# schematic.net
KiCad netlist of a schematic drawn in Altium Designer
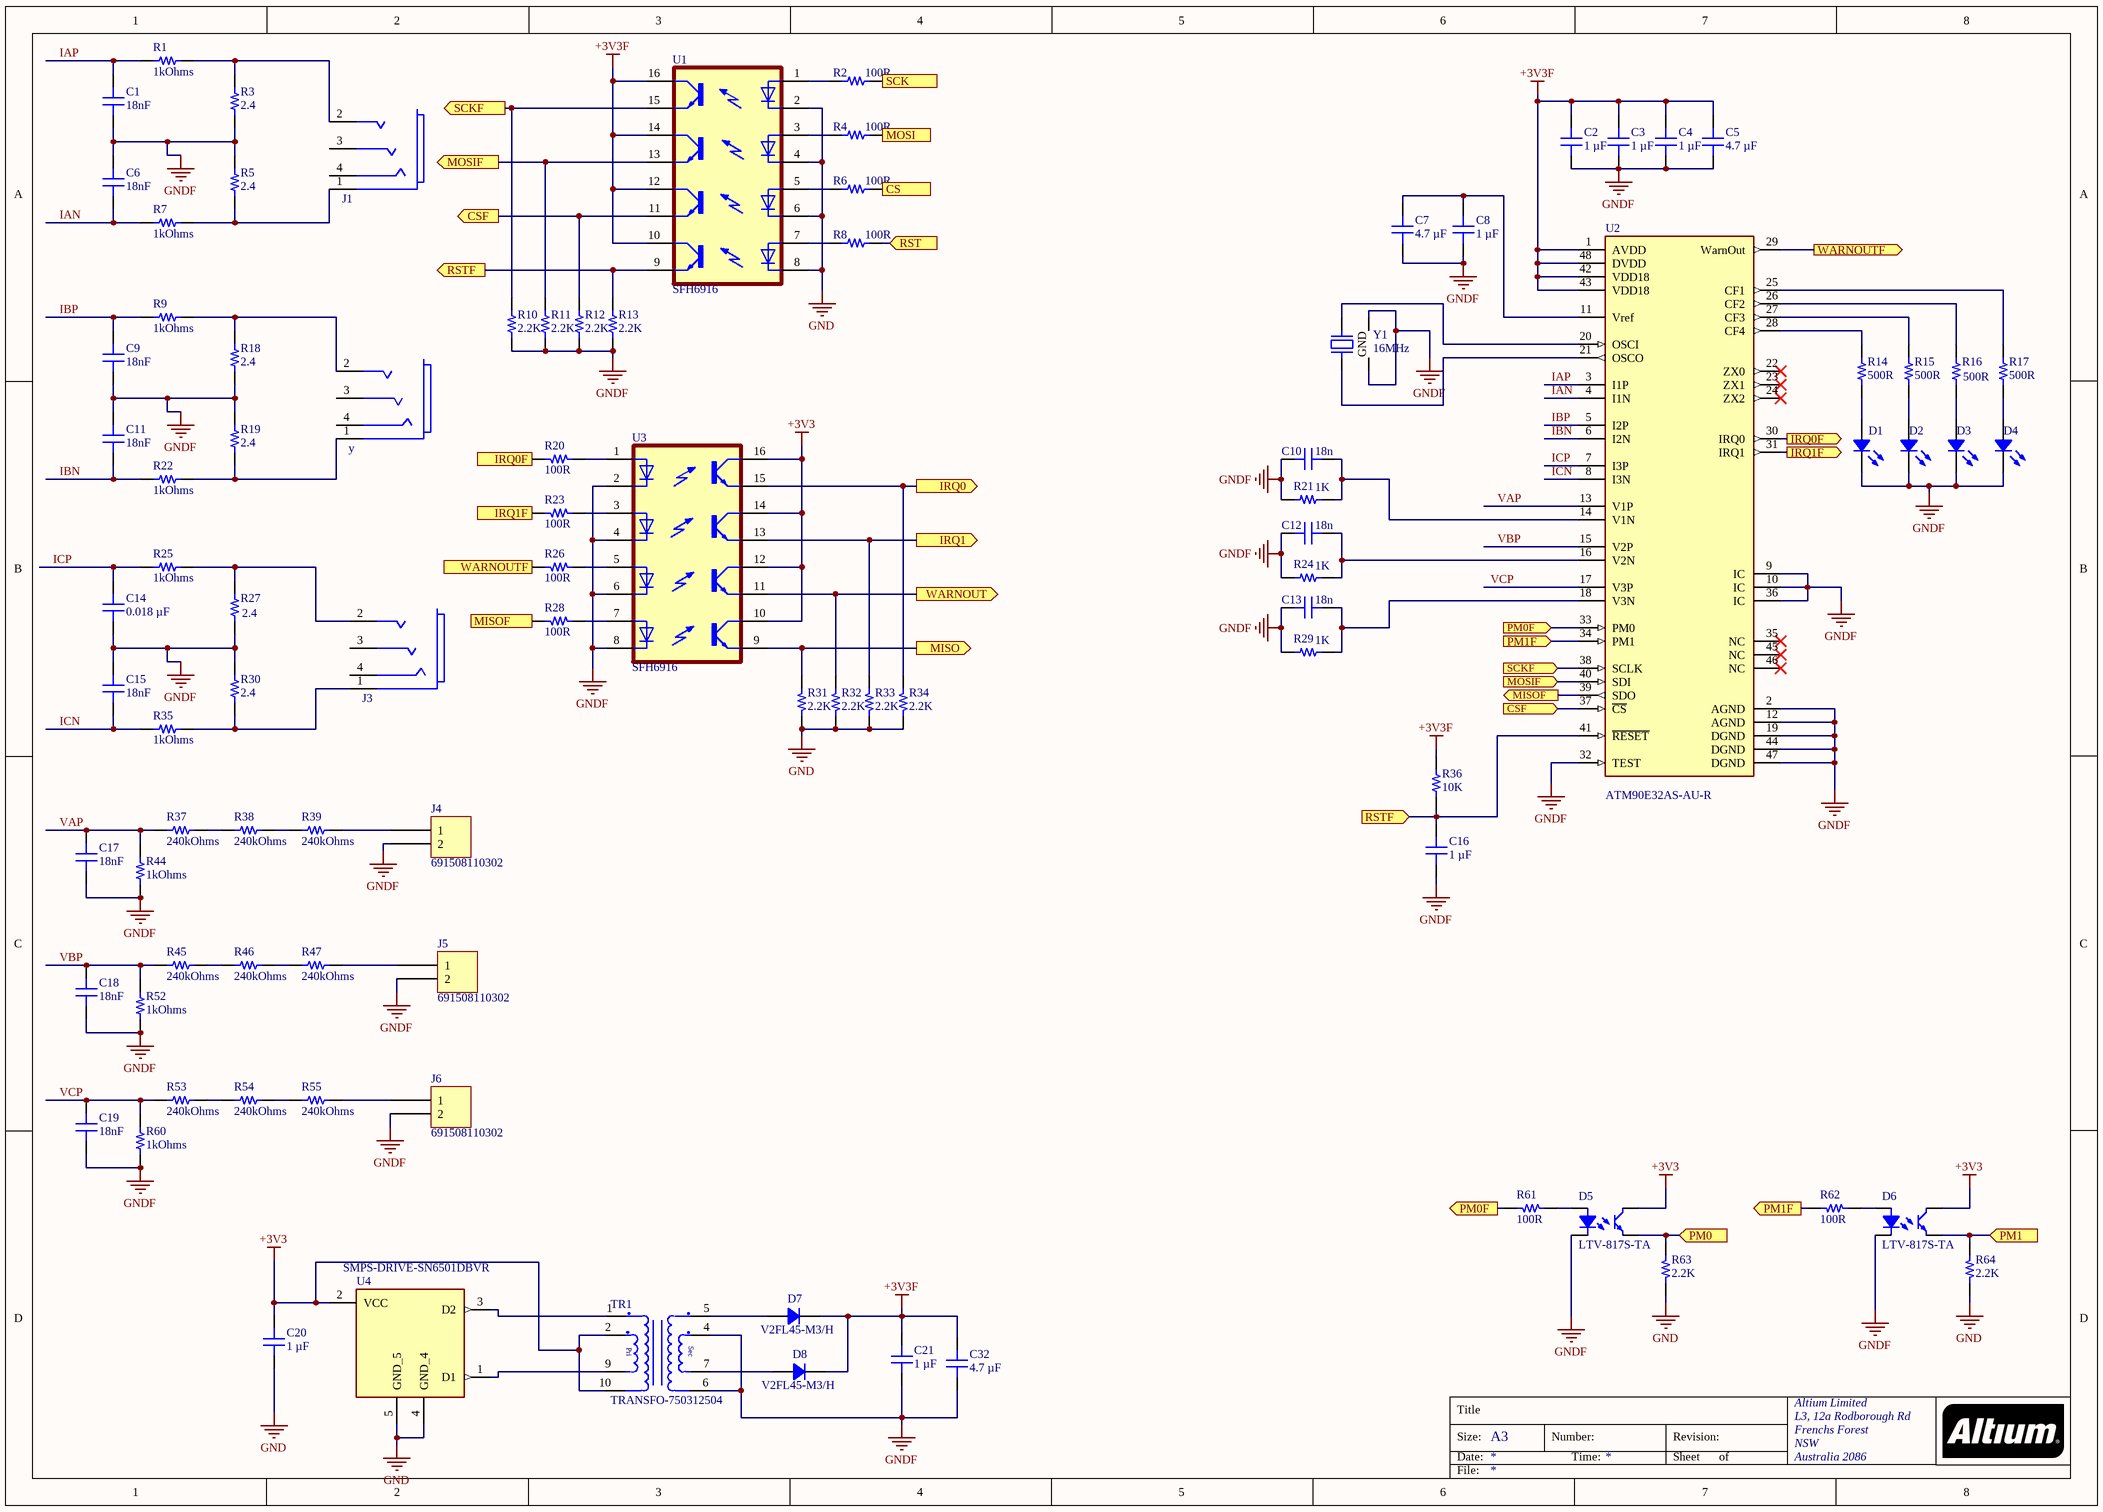
[diagram p0: schematic.SchDoc]

(export (version "E")
  (design (tool "Eeschema 10.0.6"))
  (components
    (comp (ref "C1")
      (value "18nF")
      (footprint "CAP 0805_2012")
      (description "CAP CER 10PF 250V C0G/NP0 0805")
      (fields
        (field (name "PART NUMBER") "GQM2195C2E100FB12D")
        (field (name "MANUFACTURER") "Murata Electronics")
      )
      (libsource (lib "CAL") (part "Capacitor"))
    )
    (comp (ref "C2")
      (value "1 µF")
      (footprint "CAP 0603_1608")
      (description "CAP CER 0603 1UF 16V X7R 10%")
      (fields (field (name "PART NUMBER") "C0603C105K4RACAUTO") (field (name "MANUFACTURER") "KEMET"))
      (libsource (lib "CAL") (part "Capacitor"))
    )
    (comp (ref "C3")
      (value "1 µF")
      (footprint "CAP 0603_1608")
      (description "CAP CER 0603 1UF 16V X7R 10%")
      (fields (field (name "PART NUMBER") "C0603C105K4RACAUTO") (field (name "MANUFACTURER") "KEMET"))
      (libsource (lib "CAL") (part "Capacitor"))
    )
    (comp (ref "C4")
      (value "1 µF")
      (footprint "CAP 0603_1608")
      (description "CAP CER 0603 1UF 16V X7R 10%")
      (fields (field (name "PART NUMBER") "C0603C105K4RACAUTO") (field (name "MANUFACTURER") "KEMET"))
      (libsource (lib "CAL") (part "Capacitor"))
    )
    (comp (ref "C5")
      (value "4.7 µF")
      (footprint "CAP 1206_3216 - 0.8MM")
      (description "CAP, MLCC, 1206/3216, 16V, X7R,")
      (fields (field (name "PART NUMBER") "EMF316AB7475KLHT") (field (name "MANUFACTURER") "Taiyo Yuden"))
      (libsource (lib "CAL") (part "Capacitor"))
    )
    (comp (ref "C6")
      (value "18nF")
      (footprint "CAP 0805_2012")
      (description "CAP CER 10PF 250V C0G/NP0 0805")
      (fields
        (field (name "PART NUMBER") "GQM2195C2E100FB12D")
        (field (name "MANUFACTURER") "Murata Electronics")
      )
      (libsource (lib "CAL") (part "Capacitor"))
    )
    (comp (ref "C7")
      (value "4.7 µF")
      (footprint "CAP 1206_3216 - 0.8MM")
      (description "CAP, MLCC, 1206/3216, 16V, X7R,")
      (fields (field (name "PART NUMBER") "EMF316AB7475KLHT") (field (name "MANUFACTURER") "Taiyo Yuden"))
      (libsource (lib "CAL") (part "Capacitor"))
    )
    (comp (ref "C8")
      (value "1 µF")
      (footprint "CAP 0603_1608")
      (description "CAP CER 0603 1UF 16V X7R 10%")
      (fields (field (name "PART NUMBER") "C0603C105K4RACAUTO") (field (name "MANUFACTURER") "KEMET"))
      (libsource (lib "CAL") (part "Capacitor"))
    )
    (comp (ref "C9")
      (value "18nF")
      (footprint "CAP 0805_2012")
      (description "CAP CER 10PF 250V C0G/NP0 0805")
      (fields
        (field (name "PART NUMBER") "GQM2195C2E100FB12D")
        (field (name "MANUFACTURER") "Murata Electronics")
      )
      (libsource (lib "CAL") (part "Capacitor"))
    )
    (comp (ref "C10")
      (value "18n")
      (footprint "CAP 0805_2012")
      (description "CAP CER 0.018UF 100V X7R 0805")
      (fields (field (name "PART NUMBER") "CC0805KRX7R0BB183") (field (name "MANUFACTURER") "Yageo"))
      (libsource (lib "CAL") (part "Capacitor"))
    )
    (comp (ref "C11")
      (value "18nF")
      (footprint "CAP 0805_2012")
      (description "CAP CER 10PF 250V C0G/NP0 0805")
      (fields
        (field (name "PART NUMBER") "GQM2195C2E100FB12D")
        (field (name "MANUFACTURER") "Murata Electronics")
      )
      (libsource (lib "CAL") (part "Capacitor"))
    )
    (comp (ref "C12")
      (value "18n")
      (footprint "CAP 0805_2012")
      (description "CAP CER 0.018UF 100V X7R 0805")
      (fields (field (name "PART NUMBER") "CC0805KRX7R0BB183") (field (name "MANUFACTURER") "Yageo"))
      (libsource (lib "CAL") (part "Capacitor"))
    )
    (comp (ref "C13")
      (value "18n")
      (footprint "CAP 0805_2012")
      (description "CAP CER 0.018UF 100V X7R 0805")
      (fields (field (name "PART NUMBER") "CC0805KRX7R0BB183") (field (name "MANUFACTURER") "Yageo"))
      (libsource (lib "CAL") (part "Capacitor"))
    )
    (comp (ref "C14")
      (value "0.018 µF")
      (footprint "CAP 0805_2012")
      (description "CAP CER 0.018UF 100V X7R 0805")
      (fields (field (name "PART NUMBER") "CC0805KRX7R0BB183") (field (name "MANUFACTURER") "Yageo"))
      (libsource (lib "CAL") (part "Capacitor"))
    )
    (comp (ref "C15")
      (value "18nF")
      (footprint "CAP 0805_2012")
      (description "CAP CER 10PF 250V C0G/NP0 0805")
      (fields
        (field (name "PART NUMBER") "GQM2195C2E100FB12D")
        (field (name "MANUFACTURER") "Murata Electronics")
      )
      (libsource (lib "CAL") (part "Capacitor"))
    )
    (comp (ref "C16")
      (value "1 µF")
      (footprint "CAP 0603_1608")
      (description "CAP CER 0603 1UF 16V X7R 10%")
      (fields (field (name "PART NUMBER") "C0603C105K4RACAUTO") (field (name "MANUFACTURER") "KEMET"))
      (libsource (lib "CAL") (part "Capacitor"))
    )
    (comp (ref "C17")
      (value "18nF")
      (footprint "CAP 0805_2012")
      (description "CAP CER 10PF 250V C0G/NP0 0805")
      (fields
        (field (name "PART NUMBER") "GQM2195C2E100FB12D")
        (field (name "MANUFACTURER") "Murata Electronics")
      )
      (libsource (lib "CAL") (part "Capacitor"))
    )
    (comp (ref "C18")
      (value "18nF")
      (footprint "CAP 0805_2012")
      (description "CAP CER 10PF 250V C0G/NP0 0805")
      (fields
        (field (name "PART NUMBER") "GQM2195C2E100FB12D")
        (field (name "MANUFACTURER") "Murata Electronics")
      )
      (libsource (lib "CAL") (part "Capacitor"))
    )
    (comp (ref "C19")
      (value "18nF")
      (footprint "CAP 0805_2012")
      (description "CAP CER 10PF 250V C0G/NP0 0805")
      (fields
        (field (name "PART NUMBER") "GQM2195C2E100FB12D")
        (field (name "MANUFACTURER") "Murata Electronics")
      )
      (libsource (lib "CAL") (part "Capacitor"))
    )
    (comp (ref "C20")
      (value "1 µF")
      (footprint "CAP 0805_2012")
      (description "CAP CER 1UF 16V X8R 0805")
      (fields
        (field (name "PART NUMBER") "CGA4J3X8R1C105K125AB")
        (field (name "MANUFACTURER") "TDK Corporation")
      )
      (libsource (lib "CAL") (part "Capacitor"))
    )
    (comp (ref "C21")
      (value "1 µF")
      (footprint "CAP 0805_2012")
      (description "CAP CER 1UF 16V X8R 0805")
      (fields
        (field (name "PART NUMBER") "CGA4J3X8R1C105K125AB")
        (field (name "MANUFACTURER") "TDK Corporation")
      )
      (libsource (lib "CAL") (part "Capacitor"))
    )
    (comp (ref "C32")
      (value "4.7 µF")
      (footprint "CAP 1206_3216 - 0.8MM")
      (description "CAP, MLCC, 1206/3216, 16V, X7R,")
      (fields (field (name "PART NUMBER") "EMF316AB7475KLHT") (field (name "MANUFACTURER") "Taiyo Yuden"))
      (libsource (lib "CAL") (part "Capacitor"))
    )
    (comp (ref "D1")
      (value "Yellow")
      (footprint "LED 1206_3216 YELLOW")
      (description "LED YELLOW 1206 SMD")
      (fields (field (name "PART NUMBER") "5990240007F") (field (name "MANUFACTURER") "Dialight"))
      (libsource (lib "CAL") (part "LED"))
    )
    (comp (ref "D2")
      (value "Yellow")
      (footprint "LED 1206_3216 YELLOW")
      (description "LED YELLOW 1206 SMD")
      (fields (field (name "PART NUMBER") "5990240007F") (field (name "MANUFACTURER") "Dialight"))
      (libsource (lib "CAL") (part "LED"))
    )
    (comp (ref "D3")
      (value "Yellow")
      (footprint "LED 1206_3216 YELLOW")
      (description "LED YELLOW 1206 SMD")
      (fields (field (name "PART NUMBER") "5990240007F") (field (name "MANUFACTURER") "Dialight"))
      (libsource (lib "CAL") (part "LED"))
    )
    (comp (ref "D4")
      (value "Yellow")
      (footprint "LED 1206_3216 YELLOW")
      (description "LED YELLOW 1206 SMD")
      (fields (field (name "PART NUMBER") "5990240007F") (field (name "MANUFACTURER") "Dialight"))
      (libsource (lib "CAL") (part "LED"))
    )
    (comp (ref "D5")
      (value "LTV-817S-TA")
      (footprint "LITEON LTV-817")
      (description "OPTOISOLATR 5KV TRANSISTOR 4-SMD")
      (fields (field (name "MANUFACTURER") "Lite-On Inc."))
      (libsource (lib "CAL") (part "Optoisolator"))
    )
    (comp (ref "D6")
      (value "LTV-817S-TA")
      (footprint "LITEON LTV-817")
      (description "OPTOISOLATR 5KV TRANSISTOR 4-SMD")
      (fields (field (name "MANUFACTURER") "Lite-On Inc."))
      (libsource (lib "CAL") (part "Optoisolator"))
    )
    (comp (ref "D7")
      (value "V2FL45-M3/H")
      (footprint "SMF DO-219AB")
      (description "2A,45V,SMF,TRENCH SKY RECT.")
      (fields (field (name "MANUFACTURER") "Vishay Semiconductor Diodes Division"))
      (libsource (lib "CAL") (part "Diode"))
    )
    (comp (ref "D8")
      (value "V2FL45-M3/H")
      (footprint "SMF DO-219AB")
      (description "2A,45V,SMF,TRENCH SKY RECT.")
      (fields (field (name "MANUFACTURER") "Vishay Semiconductor Diodes Division"))
      (libsource (lib "CAL") (part "Diode"))
    )
    (comp (ref "J1")
      (value "SJ2-3574A-SMT-TR")
      (footprint "CON_JACK_AUDIO_CUISJ2-3574A-SMT-TR_MFG")
      (description "3.5 mm, Stereo, Right Angle, Surface Mount (SMT), Audio Jack Connector")
      (libsource (lib "extra_components") (part "CON_JACK_AUDIO_SJ2-3574A-SMT-TR"))
    )
    (comp (ref "J3")
      (value "SJ2-3574A-SMT-TR")
      (footprint "CON_JACK_AUDIO_CUISJ2-3574A-SMT-TR_MFG")
      (description "3.5 mm, Stereo, Right Angle, Surface Mount (SMT), Audio Jack Connector")
      (libsource (lib "extra_components") (part "CON_JACK_AUDIO_SJ2-3574A-SMT-TR"))
    )
    (comp (ref "J4")
      (value "691508110302")
      (footprint "WURTH 691508110302")
      (description "TERM BLOCK 2POS 3.5MM SMD")
      (fields (field (name "MANUFACTURER") "Würth Elektronik") (field (name "VOLTAGE") "300V"))
      (libsource (lib "CAL") (part "2 Pin"))
    )
    (comp (ref "J5")
      (value "691508110302")
      (footprint "WURTH 691508110302")
      (description "TERM BLOCK 2POS 3.5MM SMD")
      (fields (field (name "MANUFACTURER") "Würth Elektronik") (field (name "VOLTAGE") "300V"))
      (libsource (lib "CAL") (part "2 Pin"))
    )
    (comp (ref "J6")
      (value "691508110302")
      (footprint "WURTH 691508110302")
      (description "TERM BLOCK 2POS 3.5MM SMD")
      (fields (field (name "MANUFACTURER") "Würth Elektronik") (field (name "VOLTAGE") "300V"))
      (libsource (lib "CAL") (part "2 Pin"))
    )
    (comp (ref "R1")
      (value "1kOhms")
      (footprint "RES 0805_2012")
      (description "RES SMD 10K OHM 1% 1/8W 0805")
      (fields (field (name "PART NUMBER") "RC0805FR-0710KP") (field (name "MANUFACTURER") "Yageo"))
      (libsource (lib "CAL") (part "Resistor"))
    )
    (comp (ref "R2")
      (value "100R")
      (footprint "RES 0805_2012")
      (description "RES SMD 100 OHM 1% 0.4W 0805")
      (fields (field (name "PART NUMBER") "RCS0805100RFKEA") (field (name "MANUFACTURER") "Vishay Dale"))
      (libsource (lib "CAL") (part "Resistor"))
    )
    (comp (ref "R3")
      (value "2.4")
      (footprint "RES 0805_2012")
      (description "RES SMD 10K OHM 1% 1/8W 0805")
      (fields (field (name "PART NUMBER") "RC0805FR-0710KP") (field (name "MANUFACTURER") "Yageo"))
      (libsource (lib "CAL") (part "Resistor"))
    )
    (comp (ref "R4")
      (value "100R")
      (footprint "RES 0805_2012")
      (description "RES SMD 100 OHM 1% 0.4W 0805")
      (fields (field (name "PART NUMBER") "RCS0805100RFKEA") (field (name "MANUFACTURER") "Vishay Dale"))
      (libsource (lib "CAL") (part "Resistor"))
    )
    (comp (ref "R5")
      (value "2.4")
      (footprint "RES 0805_2012")
      (description "RES SMD 10K OHM 1% 1/8W 0805")
      (fields (field (name "PART NUMBER") "RC0805FR-0710KP") (field (name "MANUFACTURER") "Yageo"))
      (libsource (lib "CAL") (part "Resistor"))
    )
    (comp (ref "R6")
      (value "100R")
      (footprint "RES 0805_2012")
      (description "RES SMD 100 OHM 1% 0.4W 0805")
      (fields (field (name "PART NUMBER") "RCS0805100RFKEA") (field (name "MANUFACTURER") "Vishay Dale"))
      (libsource (lib "CAL") (part "Resistor"))
    )
    (comp (ref "R7")
      (value "1kOhms")
      (footprint "RES 0805_2012")
      (description "RES SMD 10K OHM 1% 1/8W 0805")
      (fields (field (name "PART NUMBER") "RC0805FR-0710KP") (field (name "MANUFACTURER") "Yageo"))
      (libsource (lib "CAL") (part "Resistor"))
    )
    (comp (ref "R8")
      (value "100R")
      (footprint "RES 0805_2012")
      (description "RES SMD 100 OHM 1% 0.4W 0805")
      (fields (field (name "PART NUMBER") "RCS0805100RFKEA") (field (name "MANUFACTURER") "Vishay Dale"))
      (libsource (lib "CAL") (part "Resistor"))
    )
    (comp (ref "R9")
      (value "1kOhms")
      (footprint "RES 0805_2012")
      (description "RES SMD 10K OHM 1% 1/8W 0805")
      (fields (field (name "PART NUMBER") "RC0805FR-0710KP") (field (name "MANUFACTURER") "Yageo"))
      (libsource (lib "CAL") (part "Resistor"))
    )
    (comp (ref "R10")
      (value "2.2K")
      (footprint "RES 0805_2012")
      (description "RES SMD 2.2K OHM 5% 1/4W 0805")
      (fields (field (name "PART NUMBER") "SR0805JR-7W2K2L") (field (name "MANUFACTURER") "Yageo"))
      (libsource (lib "CAL") (part "Resistor"))
    )
    (comp (ref "R11")
      (value "2.2K")
      (footprint "RES 0805_2012")
      (description "RES SMD 2.2K OHM 5% 1/4W 0805")
      (fields (field (name "PART NUMBER") "SR0805JR-7W2K2L") (field (name "MANUFACTURER") "Yageo"))
      (libsource (lib "CAL") (part "Resistor"))
    )
    (comp (ref "R12")
      (value "2.2K")
      (footprint "RES 0805_2012")
      (description "RES SMD 2.2K OHM 5% 1/4W 0805")
      (fields (field (name "PART NUMBER") "SR0805JR-7W2K2L") (field (name "MANUFACTURER") "Yageo"))
      (libsource (lib "CAL") (part "Resistor"))
    )
    (comp (ref "R13")
      (value "2.2K")
      (footprint "RES 0805_2012")
      (description "RES SMD 2.2K OHM 5% 1/4W 0805")
      (fields (field (name "PART NUMBER") "SR0805JR-7W2K2L") (field (name "MANUFACTURER") "Yageo"))
      (libsource (lib "CAL") (part "Resistor"))
    )
    (comp (ref "R14")
      (value "500R")
      (footprint "RES 0805_2012")
      (description "RES SMD 500 OHM 0.05% 1/8W 0805")
      (fields (field (name "PART NUMBER") "TNPU0805500RAZEN00") (field (name "MANUFACTURER") "Vishay Dale"))
      (libsource (lib "CAL") (part "Resistor"))
    )
    (comp (ref "R15")
      (value "500R")
      (footprint "RES 0805_2012")
      (description "RES SMD 500 OHM 0.05% 1/8W 0805")
      (fields (field (name "PART NUMBER") "TNPU0805500RAZEN00") (field (name "MANUFACTURER") "Vishay Dale"))
      (libsource (lib "CAL") (part "Resistor"))
    )
    (comp (ref "R16")
      (value "500R")
      (footprint "RES 0805_2012")
      (description "RES SMD 500 OHM 0.05% 1/8W 0805")
      (fields (field (name "PART NUMBER") "TNPU0805500RAZEN00") (field (name "MANUFACTURER") "Vishay Dale"))
      (libsource (lib "CAL") (part "Resistor"))
    )
    (comp (ref "R17")
      (value "500R")
      (footprint "RES 0805_2012")
      (description "RES SMD 500 OHM 0.05% 1/8W 0805")
      (fields (field (name "PART NUMBER") "TNPU0805500RAZEN00") (field (name "MANUFACTURER") "Vishay Dale"))
      (libsource (lib "CAL") (part "Resistor"))
    )
    (comp (ref "R18")
      (value "2.4")
      (footprint "RES 0805_2012")
      (description "RES SMD 10K OHM 1% 1/8W 0805")
      (fields (field (name "PART NUMBER") "RC0805FR-0710KP") (field (name "MANUFACTURER") "Yageo"))
      (libsource (lib "CAL") (part "Resistor"))
    )
    (comp (ref "R19")
      (value "2.4")
      (footprint "RES 0805_2012")
      (description "RES SMD 10K OHM 1% 1/8W 0805")
      (fields (field (name "PART NUMBER") "RC0805FR-0710KP") (field (name "MANUFACTURER") "Yageo"))
      (libsource (lib "CAL") (part "Resistor"))
    )
    (comp (ref "R20")
      (value "100R")
      (footprint "RES 0805_2012")
      (description "RES SMD 100 OHM 1% 0.4W 0805")
      (fields (field (name "PART NUMBER") "RCS0805100RFKEA") (field (name "MANUFACTURER") "Vishay Dale"))
      (libsource (lib "CAL") (part "Resistor"))
    )
    (comp (ref "R21")
      (value "1K")
      (footprint "RES 0805_2012")
      (description "RES 1K OHM 0.1% 1/10W 0805")
      (fields
        (field (name "PART NUMBER") "RNCS0805BKE1K00")
        (field (name "MANUFACTURER") "Stackpole Electronics Inc")
      )
      (libsource (lib "CAL") (part "Resistor"))
    )
    (comp (ref "R22")
      (value "1kOhms")
      (footprint "RES 0805_2012")
      (description "RES SMD 10K OHM 1% 1/8W 0805")
      (fields (field (name "PART NUMBER") "RC0805FR-0710KP") (field (name "MANUFACTURER") "Yageo"))
      (libsource (lib "CAL") (part "Resistor"))
    )
    (comp (ref "R23")
      (value "100R")
      (footprint "RES 0805_2012")
      (description "RES SMD 100 OHM 1% 0.4W 0805")
      (fields (field (name "PART NUMBER") "RCS0805100RFKEA") (field (name "MANUFACTURER") "Vishay Dale"))
      (libsource (lib "CAL") (part "Resistor"))
    )
    (comp (ref "R24")
      (value "1K")
      (footprint "RES 0805_2012")
      (description "RES 1K OHM 0.1% 1/10W 0805")
      (fields
        (field (name "PART NUMBER") "RNCS0805BKE1K00")
        (field (name "MANUFACTURER") "Stackpole Electronics Inc")
      )
      (libsource (lib "CAL") (part "Resistor"))
    )
    (comp (ref "R25")
      (value "1kOhms")
      (footprint "RES 0805_2012")
      (description "RES SMD 10K OHM 1% 1/8W 0805")
      (fields (field (name "PART NUMBER") "RC0805FR-0710KP") (field (name "MANUFACTURER") "Yageo"))
      (libsource (lib "CAL") (part "Resistor"))
    )
    (comp (ref "R26")
      (value "100R")
      (footprint "RES 0805_2012")
      (description "RES SMD 100 OHM 1% 0.4W 0805")
      (fields (field (name "PART NUMBER") "RCS0805100RFKEA") (field (name "MANUFACTURER") "Vishay Dale"))
      (libsource (lib "CAL") (part "Resistor"))
    )
    (comp (ref "R27")
      (value "2.4")
      (footprint "RES 0805_2012")
      (description "RES SMD 10K OHM 1% 1/8W 0805")
      (fields (field (name "PART NUMBER") "RC0805FR-0710KP") (field (name "MANUFACTURER") "Yageo"))
      (libsource (lib "CAL") (part "Resistor"))
    )
    (comp (ref "R28")
      (value "100R")
      (footprint "RES 0805_2012")
      (description "RES SMD 100 OHM 1% 0.4W 0805")
      (fields (field (name "PART NUMBER") "RCS0805100RFKEA") (field (name "MANUFACTURER") "Vishay Dale"))
      (libsource (lib "CAL") (part "Resistor"))
    )
    (comp (ref "R29")
      (value "1K")
      (footprint "RES 0805_2012")
      (description "RES 1K OHM 0.1% 1/10W 0805")
      (fields
        (field (name "PART NUMBER") "RNCS0805BKE1K00")
        (field (name "MANUFACTURER") "Stackpole Electronics Inc")
      )
      (libsource (lib "CAL") (part "Resistor"))
    )
    (comp (ref "R30")
      (value "2.4")
      (footprint "RES 0805_2012")
      (description "RES SMD 10K OHM 1% 1/8W 0805")
      (fields (field (name "PART NUMBER") "RC0805FR-0710KP") (field (name "MANUFACTURER") "Yageo"))
      (libsource (lib "CAL") (part "Resistor"))
    )
    (comp (ref "R31")
      (value "2.2K")
      (footprint "RES 0805_2012")
      (description "RES SMD 2.2K OHM 5% 1/4W 0805")
      (fields (field (name "PART NUMBER") "SR0805JR-7W2K2L") (field (name "MANUFACTURER") "Yageo"))
      (libsource (lib "CAL") (part "Resistor"))
    )
    (comp (ref "R32")
      (value "2.2K")
      (footprint "RES 0805_2012")
      (description "RES SMD 2.2K OHM 5% 1/4W 0805")
      (fields (field (name "PART NUMBER") "SR0805JR-7W2K2L") (field (name "MANUFACTURER") "Yageo"))
      (libsource (lib "CAL") (part "Resistor"))
    )
    (comp (ref "R33")
      (value "2.2K")
      (footprint "RES 0805_2012")
      (description "RES SMD 2.2K OHM 5% 1/4W 0805")
      (fields (field (name "PART NUMBER") "SR0805JR-7W2K2L") (field (name "MANUFACTURER") "Yageo"))
      (libsource (lib "CAL") (part "Resistor"))
    )
    (comp (ref "R34")
      (value "2.2K")
      (footprint "RES 0805_2012")
      (description "RES SMD 2.2K OHM 5% 1/4W 0805")
      (fields (field (name "PART NUMBER") "SR0805JR-7W2K2L") (field (name "MANUFACTURER") "Yageo"))
      (libsource (lib "CAL") (part "Resistor"))
    )
    (comp (ref "R35")
      (value "1kOhms")
      (footprint "RES 0805_2012")
      (description "RES SMD 10K OHM 1% 1/8W 0805")
      (fields (field (name "PART NUMBER") "RC0805FR-0710KP") (field (name "MANUFACTURER") "Yageo"))
      (libsource (lib "CAL") (part "Resistor"))
    )
    (comp (ref "R36")
      (value "10K")
      (footprint "RES 0805_2012")
      (description "RES 10K OHM 0.1% 1/10W 0805")
      (fields
        (field (name "PART NUMBER") "RNCS0805BKE10K0")
        (field (name "MANUFACTURER") "Stackpole Electronics Inc")
      )
      (libsource (lib "CAL") (part "Resistor"))
    )
    (comp (ref "R37")
      (value "240kOhms")
      (footprint "RES 0805_2012")
      (description "RES SMD 10K OHM 1% 1/8W 0805")
      (fields (field (name "PART NUMBER") "RC0805FR-0710KP") (field (name "MANUFACTURER") "Yageo"))
      (libsource (lib "CAL") (part "Resistor"))
    )
    (comp (ref "R38")
      (value "240kOhms")
      (footprint "RES 0805_2012")
      (description "RES SMD 10K OHM 1% 1/8W 0805")
      (fields (field (name "PART NUMBER") "RC0805FR-0710KP") (field (name "MANUFACTURER") "Yageo"))
      (libsource (lib "CAL") (part "Resistor"))
    )
    (comp (ref "R39")
      (value "240kOhms")
      (footprint "RES 0805_2012")
      (description "RES SMD 10K OHM 1% 1/8W 0805")
      (fields (field (name "PART NUMBER") "RC0805FR-0710KP") (field (name "MANUFACTURER") "Yageo"))
      (libsource (lib "CAL") (part "Resistor"))
    )
    (comp (ref "R44")
      (value "1kOhms")
      (footprint "RES 0805_2012")
      (description "RES SMD 10K OHM 1% 1/8W 0805")
      (fields (field (name "PART NUMBER") "RC0805FR-0710KP") (field (name "MANUFACTURER") "Yageo"))
      (libsource (lib "CAL") (part "Resistor"))
    )
    (comp (ref "R45")
      (value "240kOhms")
      (footprint "RES 0805_2012")
      (description "RES SMD 10K OHM 1% 1/8W 0805")
      (fields (field (name "PART NUMBER") "RC0805FR-0710KP") (field (name "MANUFACTURER") "Yageo"))
      (libsource (lib "CAL") (part "Resistor"))
    )
    (comp (ref "R46")
      (value "240kOhms")
      (footprint "RES 0805_2012")
      (description "RES SMD 10K OHM 1% 1/8W 0805")
      (fields (field (name "PART NUMBER") "RC0805FR-0710KP") (field (name "MANUFACTURER") "Yageo"))
      (libsource (lib "CAL") (part "Resistor"))
    )
    (comp (ref "R47")
      (value "240kOhms")
      (footprint "RES 0805_2012")
      (description "RES SMD 10K OHM 1% 1/8W 0805")
      (fields (field (name "PART NUMBER") "RC0805FR-0710KP") (field (name "MANUFACTURER") "Yageo"))
      (libsource (lib "CAL") (part "Resistor"))
    )
    (comp (ref "R52")
      (value "1kOhms")
      (footprint "RES 0805_2012")
      (description "RES SMD 10K OHM 1% 1/8W 0805")
      (fields (field (name "PART NUMBER") "RC0805FR-0710KP") (field (name "MANUFACTURER") "Yageo"))
      (libsource (lib "CAL") (part "Resistor"))
    )
    (comp (ref "R53")
      (value "240kOhms")
      (footprint "RES 0805_2012")
      (description "RES SMD 10K OHM 1% 1/8W 0805")
      (fields (field (name "PART NUMBER") "RC0805FR-0710KP") (field (name "MANUFACTURER") "Yageo"))
      (libsource (lib "CAL") (part "Resistor"))
    )
    (comp (ref "R54")
      (value "240kOhms")
      (footprint "RES 0805_2012")
      (description "RES SMD 10K OHM 1% 1/8W 0805")
      (fields (field (name "PART NUMBER") "RC0805FR-0710KP") (field (name "MANUFACTURER") "Yageo"))
      (libsource (lib "CAL") (part "Resistor"))
    )
    (comp (ref "R55")
      (value "240kOhms")
      (footprint "RES 0805_2012")
      (description "RES SMD 10K OHM 1% 1/8W 0805")
      (fields (field (name "PART NUMBER") "RC0805FR-0710KP") (field (name "MANUFACTURER") "Yageo"))
      (libsource (lib "CAL") (part "Resistor"))
    )
    (comp (ref "R60")
      (value "1kOhms")
      (footprint "RES 0805_2012")
      (description "RES SMD 10K OHM 1% 1/8W 0805")
      (fields (field (name "PART NUMBER") "RC0805FR-0710KP") (field (name "MANUFACTURER") "Yageo"))
      (libsource (lib "CAL") (part "Resistor"))
    )
    (comp (ref "R61")
      (value "100R")
      (footprint "RES 0805_2012")
      (description "RES SMD 100 OHM 1% 0.4W 0805")
      (fields (field (name "PART NUMBER") "RCS0805100RFKEA") (field (name "MANUFACTURER") "Vishay Dale"))
      (libsource (lib "CAL") (part "Resistor"))
    )
    (comp (ref "R62")
      (value "100R")
      (footprint "RES 0805_2012")
      (description "RES SMD 100 OHM 1% 0.4W 0805")
      (fields (field (name "PART NUMBER") "RCS0805100RFKEA") (field (name "MANUFACTURER") "Vishay Dale"))
      (libsource (lib "CAL") (part "Resistor"))
    )
    (comp (ref "R63")
      (value "2.2K")
      (footprint "RES 0805_2012")
      (description "RES SMD 2.2K OHM 5% 1/4W 0805")
      (fields (field (name "PART NUMBER") "SR0805JR-7W2K2L") (field (name "MANUFACTURER") "Yageo"))
      (libsource (lib "CAL") (part "Resistor"))
    )
    (comp (ref "R64")
      (value "2.2K")
      (footprint "RES 0805_2012")
      (description "RES SMD 2.2K OHM 5% 1/4W 0805")
      (fields (field (name "PART NUMBER") "SR0805JR-7W2K2L") (field (name "MANUFACTURER") "Yageo"))
      (libsource (lib "CAL") (part "Resistor"))
    )
    (comp (ref "TR1")
      (value "TRANSFO-750312504")
      (footprint "TRANSFO-750312504")
      (description "Capacitor Charger For For DC/DC Converters SMPS Transformer 500VDC Isolation - Surface Mount")
      (libsource (lib "extra_components") (part "TRANSFO-750312504"))
    )
    (comp (ref "U1")
      (value "SFH6916")
      (footprint "SOIC127P686X203-16N")
      (fields (field (name "MF") "{'manufacturer': u'Vishay'}"))
      (libsource (lib "extra_components") (part "SFH6916"))
    )
    (comp (ref "U2")
      (value "ATM90E32AS-AU-R")
      (footprint "Microchip_TQFP48_IPC_A - duplicate")
      (description "Smart Energy SoC, 3 - 3.6 VCC, -40 to 85 degC, TQFP-48, RoHS")
      (fields (field (name "SUPPLIER PART NUMBER 1") "ATM90E32AS-AU-R"))
      (libsource (lib "extra_components") (part "ATM90E32AS-AU-R"))
    )
    (comp (ref "U3")
      (value "SFH6916")
      (footprint "SOIC127P686X203-16N")
      (fields (field (name "MF") "{'manufacturer': u'Vishay'}"))
      (libsource (lib "extra_components") (part "SFH6916"))
    )
    (comp (ref "U4")
      (value "SMPS-DRIVE-SN6501DBVR")
      (footprint "SMPS-DRIVE-SOT95P280X145-5N")
      (description "Low-noise, 350-mA, 410-kHz transformer driver for isolated power supplies 5-SOT-23 -40 to 125")
      (fields (field (name "MP") "SN6501DBVR") (field (name "MF") "Texas Instruments"))
      (libsource (lib "extra_components") (part "SMPS-DRIVE-SN6501DBVR"))
    )
    (comp (ref "y")
      (value "SJ2-3574A-SMT-TR")
      (footprint "CON_JACK_AUDIO_CUISJ2-3574A-SMT-TR_MFG")
      (description "3.5 mm, Stereo, Right Angle, Surface Mount (SMT), Audio Jack Connector")
      (libsource (lib "extra_components") (part "CON_JACK_AUDIO_SJ2-3574A-SMT-TR"))
    )
    (comp (ref "Y1")
      (value "16MHz")
      (footprint "EPSON TSX-3225")
      (description "CRYSTAL 16.0000MHZ 9PF SMD")
      (fields (field (name "PART NUMBER") "TSX-3225 16.0000MF18X-AC3") (field (name "MANUFACTURER") "EPSON"))
      (libsource (lib "CAL") (part "Epson Crystal TSX-3225"))
    )
  )
  (nets
    (net (code "1") (name "+3V3") (class "Default")
      (node (ref "C20") (pin "2") (pinfunction "2_2") (pintype "passive"))
      (node (ref "D5") (pin "4") (pinfunction "4_4") (pintype "passive"))
      (node (ref "D6") (pin "4") (pinfunction "4_4") (pintype "passive"))
      (node (ref "TR1") (pin "10") (pinfunction "10_10") (pintype "passive"))
      (node (ref "TR1") (pin "2") (pinfunction "2_2") (pintype "passive"))
      (node (ref "U3") (pin "10") (pinfunction "CO4_10") (pintype "passive"))
      (node (ref "U3") (pin "12") (pinfunction "CO3_12") (pintype "passive"))
      (node (ref "U3") (pin "14") (pinfunction "CO2_14") (pintype "passive"))
      (node (ref "U3") (pin "16") (pinfunction "CO1_16") (pintype "passive"))
      (node (ref "U4") (pin "2") (pinfunction "VCC_2") (pintype "power_in"))
    )
    (net (code "2") (name "+3V3F") (class "Default")
      (node (ref "C2") (pin "2") (pinfunction "2_2") (pintype "passive"))
      (node (ref "C21") (pin "2") (pinfunction "2_2") (pintype "passive"))
      (node (ref "C3") (pin "2") (pinfunction "2_2") (pintype "passive"))
      (node (ref "C32") (pin "2") (pinfunction "2_2") (pintype "passive"))
      (node (ref "C4") (pin "2") (pinfunction "2_2") (pintype "passive"))
      (node (ref "C5") (pin "2") (pinfunction "2_2") (pintype "passive"))
      (node (ref "D7") (pin "2") (pinfunction "2_2") (pintype "passive"))
      (node (ref "D8") (pin "2") (pinfunction "2_2") (pintype "passive"))
      (node (ref "R36") (pin "2") (pinfunction "2_2") (pintype "passive"))
      (node (ref "U1") (pin "10") (pinfunction "CO4_10") (pintype "passive"))
      (node (ref "U1") (pin "12") (pinfunction "CO3_12") (pintype "passive"))
      (node (ref "U1") (pin "14") (pinfunction "CO2_14") (pintype "passive"))
      (node (ref "U1") (pin "16") (pinfunction "CO1_16") (pintype "passive"))
      (node (ref "U2") (pin "1") (pinfunction "AVDD_1") (pintype "power_in"))
      (node (ref "U2") (pin "42") (pinfunction "VDD18_42") (pintype "power_in"))
      (node (ref "U2") (pin "43") (pinfunction "VDD18_43") (pintype "power_in"))
      (node (ref "U2") (pin "48") (pinfunction "DVDD_48") (pintype "power_in"))
    )
    (net (code "3") (name "/CS") (class "Default")
      (node (ref "R6") (pin "2") (pinfunction "2_2") (pintype "passive"))
    )
    (net (code "4") (name "/CSF") (class "Default")
      (node (ref "R12") (pin "2") (pinfunction "2_2") (pintype "passive"))
      (node (ref "U1") (pin "11") (pinfunction "E3_11") (pintype "passive"))
      (node (ref "U2") (pin "37") (pinfunction "~{CS}_37") (pintype "input"))
    )
    (net (code "5") (name "/IAN") (class "Default")
      (node (ref "C6") (pin "2") (pinfunction "2_2") (pintype "passive"))
      (node (ref "R7") (pin "2") (pinfunction "2_2") (pintype "passive"))
      (node (ref "U2") (pin "4") (pinfunction "I1N_4") (pintype "passive"))
    )
    (net (code "6") (name "/IAP") (class "Default")
      (node (ref "C1") (pin "1") (pinfunction "1_1") (pintype "passive"))
      (node (ref "R1") (pin "2") (pinfunction "2_2") (pintype "passive"))
      (node (ref "U2") (pin "3") (pinfunction "I1P_3") (pintype "passive"))
    )
    (net (code "7") (name "/IBN") (class "Default")
      (node (ref "C11") (pin "2") (pinfunction "2_2") (pintype "passive"))
      (node (ref "R22") (pin "2") (pinfunction "2_2") (pintype "passive"))
      (node (ref "U2") (pin "6") (pinfunction "I2N_6") (pintype "passive"))
    )
    (net (code "8") (name "/IBP") (class "Default")
      (node (ref "C9") (pin "1") (pinfunction "1_1") (pintype "passive"))
      (node (ref "R9") (pin "2") (pinfunction "2_2") (pintype "passive"))
      (node (ref "U2") (pin "5") (pinfunction "I2P_5") (pintype "passive"))
    )
    (net (code "9") (name "/ICN") (class "Default")
      (node (ref "C15") (pin "2") (pinfunction "2_2") (pintype "passive"))
      (node (ref "R35") (pin "2") (pinfunction "2_2") (pintype "passive"))
      (node (ref "U2") (pin "8") (pinfunction "I3N_8") (pintype "passive"))
    )
    (net (code "10") (name "/ICP") (class "Default")
      (node (ref "C14") (pin "2") (pinfunction "2_2") (pintype "passive"))
      (node (ref "R25") (pin "2") (pinfunction "2_2") (pintype "passive"))
      (node (ref "U2") (pin "7") (pinfunction "I3P_7") (pintype "passive"))
    )
    (net (code "11") (name "/IRQ0") (class "Default")
      (node (ref "R34") (pin "2") (pinfunction "2_2") (pintype "passive"))
      (node (ref "U3") (pin "15") (pinfunction "E1_15") (pintype "passive"))
    )
    (net (code "12") (name "/IRQ0F") (class "Default")
      (node (ref "R20") (pin "2") (pinfunction "2_2") (pintype "passive"))
      (node (ref "U2") (pin "30") (pinfunction "IRQ0_30") (pintype "output"))
    )
    (net (code "13") (name "/IRQ1") (class "Default")
      (node (ref "R33") (pin "2") (pinfunction "2_2") (pintype "passive"))
      (node (ref "U3") (pin "13") (pinfunction "E2_13") (pintype "passive"))
    )
    (net (code "14") (name "/IRQ1F") (class "Default")
      (node (ref "R23") (pin "2") (pinfunction "2_2") (pintype "passive"))
      (node (ref "U2") (pin "31") (pinfunction "IRQ1_31") (pintype "output"))
    )
    (net (code "15") (name "/MISO") (class "Default")
      (node (ref "R31") (pin "2") (pinfunction "2_2") (pintype "passive"))
      (node (ref "U3") (pin "9") (pinfunction "E4_9") (pintype "passive"))
    )
    (net (code "16") (name "/MISOF") (class "Default")
      (node (ref "R28") (pin "2") (pinfunction "2_2") (pintype "passive"))
      (node (ref "U2") (pin "39") (pinfunction "SDO_39") (pintype "output"))
    )
    (net (code "17") (name "/MOSI") (class "Default")
      (node (ref "R4") (pin "2") (pinfunction "2_2") (pintype "passive"))
    )
    (net (code "18") (name "/MOSIF") (class "Default")
      (node (ref "R11") (pin "2") (pinfunction "2_2") (pintype "passive"))
      (node (ref "U1") (pin "13") (pinfunction "E2_13") (pintype "passive"))
      (node (ref "U2") (pin "40") (pinfunction "SDI_40") (pintype "input"))
    )
    (net (code "19") (name "/PM0") (class "Default")
      (node (ref "D5") (pin "3") (pinfunction "3_3") (pintype "passive"))
      (node (ref "R63") (pin "2") (pinfunction "2_2") (pintype "passive"))
    )
    (net (code "20") (name "/PM0F") (class "Default")
      (node (ref "R61") (pin "2") (pinfunction "2_2") (pintype "passive"))
      (node (ref "U2") (pin "33") (pinfunction "PM0_33") (pintype "input"))
    )
    (net (code "21") (name "/PM1") (class "Default")
      (node (ref "D6") (pin "3") (pinfunction "3_3") (pintype "passive"))
      (node (ref "R64") (pin "2") (pinfunction "2_2") (pintype "passive"))
    )
    (net (code "22") (name "/PM1F") (class "Default")
      (node (ref "R62") (pin "2") (pinfunction "2_2") (pintype "passive"))
      (node (ref "U2") (pin "34") (pinfunction "PM1_34") (pintype "input"))
    )
    (net (code "23") (name "/RST") (class "Default")
      (node (ref "R8") (pin "2") (pinfunction "2_2") (pintype "passive"))
    )
    (net (code "24") (name "/RSTF") (class "Default")
      (node (ref "C16") (pin "2") (pinfunction "2_2") (pintype "passive"))
      (node (ref "R13") (pin "2") (pinfunction "2_2") (pintype "passive"))
      (node (ref "R36") (pin "1") (pinfunction "1_1") (pintype "passive"))
      (node (ref "U1") (pin "9") (pinfunction "E4_9") (pintype "passive"))
      (node (ref "U2") (pin "41") (pinfunction "~{RESET}_41") (pintype "input"))
    )
    (net (code "25") (name "/SCK") (class "Default")
      (node (ref "R2") (pin "2") (pinfunction "2_2") (pintype "passive"))
    )
    (net (code "26") (name "/SCKF") (class "Default")
      (node (ref "R10") (pin "2") (pinfunction "2_2") (pintype "passive"))
      (node (ref "U1") (pin "15") (pinfunction "E1_15") (pintype "passive"))
      (node (ref "U2") (pin "38") (pinfunction "SCLK_38") (pintype "input"))
    )
    (net (code "27") (name "/VAP") (class "Default")
      (node (ref "C17") (pin "2") (pinfunction "2_2") (pintype "passive"))
      (node (ref "R37") (pin "1") (pinfunction "1_1") (pintype "passive"))
      (node (ref "R44") (pin "2") (pinfunction "2_2") (pintype "passive"))
      (node (ref "U2") (pin "13") (pinfunction "V1P_13") (pintype "passive"))
    )
    (net (code "28") (name "/VBP") (class "Default")
      (node (ref "C18") (pin "2") (pinfunction "2_2") (pintype "passive"))
      (node (ref "R45") (pin "1") (pinfunction "1_1") (pintype "passive"))
      (node (ref "R52") (pin "2") (pinfunction "2_2") (pintype "passive"))
      (node (ref "U2") (pin "15") (pinfunction "V2P_15") (pintype "passive"))
    )
    (net (code "29") (name "/VCP") (class "Default")
      (node (ref "C19") (pin "2") (pinfunction "2_2") (pintype "passive"))
      (node (ref "R53") (pin "1") (pinfunction "1_1") (pintype "passive"))
      (node (ref "R60") (pin "2") (pinfunction "2_2") (pintype "passive"))
      (node (ref "U2") (pin "17") (pinfunction "V3P_17") (pintype "passive"))
    )
    (net (code "30") (name "/WARNOUT") (class "Default")
      (node (ref "R32") (pin "2") (pinfunction "2_2") (pintype "passive"))
      (node (ref "U3") (pin "11") (pinfunction "E3_11") (pintype "passive"))
    )
    (net (code "31") (name "/WARNOUTF") (class "Default")
      (node (ref "R26") (pin "2") (pinfunction "2_2") (pintype "passive"))
      (node (ref "U2") (pin "29") (pinfunction "WarnOut_29") (pintype "output"))
    )
    (net (code "32") (name "GND") (class "Default")
      (node (ref "C20") (pin "1") (pinfunction "1_1") (pintype "passive"))
      (node (ref "R31") (pin "1") (pinfunction "1_1") (pintype "passive"))
      (node (ref "R32") (pin "1") (pinfunction "1_1") (pintype "passive"))
      (node (ref "R33") (pin "1") (pinfunction "1_1") (pintype "passive"))
      (node (ref "R34") (pin "1") (pinfunction "1_1") (pintype "passive"))
      (node (ref "R63") (pin "1") (pinfunction "1_1") (pintype "passive"))
      (node (ref "R64") (pin "1") (pinfunction "1_1") (pintype "passive"))
      (node (ref "U1") (pin "2") (pinfunction "C1_2") (pintype "passive"))
      (node (ref "U1") (pin "4") (pinfunction "C2_4") (pintype "passive"))
      (node (ref "U1") (pin "6") (pinfunction "C3_6") (pintype "passive"))
      (node (ref "U1") (pin "8") (pinfunction "C4_8") (pintype "passive"))
      (node (ref "U4") (pin "4") (pinfunction "GND_4_4") (pintype "power_in"))
      (node (ref "U4") (pin "5") (pinfunction "GND_5_5") (pintype "power_in"))
    )
    (net (code "33") (name "GNDF") (class "Default")
      (node (ref "C1") (pin "2") (pinfunction "2_2") (pintype "passive"))
      (node (ref "C10") (pin "1") (pinfunction "1_1") (pintype "passive"))
      (node (ref "C11") (pin "1") (pinfunction "1_1") (pintype "passive"))
      (node (ref "C12") (pin "1") (pinfunction "1_1") (pintype "passive"))
      (node (ref "C13") (pin "1") (pinfunction "1_1") (pintype "passive"))
      (node (ref "C14") (pin "1") (pinfunction "1_1") (pintype "passive"))
      (node (ref "C15") (pin "1") (pinfunction "1_1") (pintype "passive"))
      (node (ref "C16") (pin "1") (pinfunction "1_1") (pintype "passive"))
      (node (ref "C17") (pin "1") (pinfunction "1_1") (pintype "passive"))
      (node (ref "C18") (pin "1") (pinfunction "1_1") (pintype "passive"))
      (node (ref "C19") (pin "1") (pinfunction "1_1") (pintype "passive"))
      (node (ref "C2") (pin "1") (pinfunction "1_1") (pintype "passive"))
      (node (ref "C21") (pin "1") (pinfunction "1_1") (pintype "passive"))
      (node (ref "C3") (pin "1") (pinfunction "1_1") (pintype "passive"))
      (node (ref "C32") (pin "1") (pinfunction "1_1") (pintype "passive"))
      (node (ref "C4") (pin "1") (pinfunction "1_1") (pintype "passive"))
      (node (ref "C5") (pin "1") (pinfunction "1_1") (pintype "passive"))
      (node (ref "C6") (pin "1") (pinfunction "1_1") (pintype "passive"))
      (node (ref "C7") (pin "1") (pinfunction "1_1") (pintype "passive"))
      (node (ref "C8") (pin "1") (pinfunction "1_1") (pintype "passive"))
      (node (ref "C9") (pin "2") (pinfunction "2_2") (pintype "passive"))
      (node (ref "D1") (pin "2") (pinfunction "2_2") (pintype "passive"))
      (node (ref "D2") (pin "2") (pinfunction "2_2") (pintype "passive"))
      (node (ref "D3") (pin "2") (pinfunction "2_2") (pintype "passive"))
      (node (ref "D4") (pin "2") (pinfunction "2_2") (pintype "passive"))
      (node (ref "D5") (pin "2") (pinfunction "2_2") (pintype "passive"))
      (node (ref "D6") (pin "2") (pinfunction "2_2") (pintype "passive"))
      (node (ref "J4") (pin "2") (pinfunction "2_2") (pintype "passive"))
      (node (ref "J5") (pin "2") (pinfunction "2_2") (pintype "passive"))
      (node (ref "J6") (pin "2") (pinfunction "2_2") (pintype "passive"))
      (node (ref "R10") (pin "1") (pinfunction "1_1") (pintype "passive"))
      (node (ref "R11") (pin "1") (pinfunction "1_1") (pintype "passive"))
      (node (ref "R12") (pin "1") (pinfunction "1_1") (pintype "passive"))
      (node (ref "R13") (pin "1") (pinfunction "1_1") (pintype "passive"))
      (node (ref "R18") (pin "2") (pinfunction "2_2") (pintype "passive"))
      (node (ref "R19") (pin "1") (pinfunction "1_1") (pintype "passive"))
      (node (ref "R21") (pin "1") (pinfunction "1_1") (pintype "passive"))
      (node (ref "R24") (pin "1") (pinfunction "1_1") (pintype "passive"))
      (node (ref "R27") (pin "2") (pinfunction "2_2") (pintype "passive"))
      (node (ref "R29") (pin "1") (pinfunction "1_1") (pintype "passive"))
      (node (ref "R3") (pin "2") (pinfunction "2_2") (pintype "passive"))
      (node (ref "R30") (pin "1") (pinfunction "1_1") (pintype "passive"))
      (node (ref "R44") (pin "1") (pinfunction "1_1") (pintype "passive"))
      (node (ref "R5") (pin "1") (pinfunction "1_1") (pintype "passive"))
      (node (ref "R52") (pin "1") (pinfunction "1_1") (pintype "passive"))
      (node (ref "R60") (pin "1") (pinfunction "1_1") (pintype "passive"))
      (node (ref "TR1") (pin "4") (pinfunction "4_4") (pintype "passive"))
      (node (ref "TR1") (pin "6") (pinfunction "6_6") (pintype "passive"))
      (node (ref "U2") (pin "10") (pinfunction "IC_10") (pintype "passive"))
      (node (ref "U2") (pin "12") (pinfunction "AGND_12") (pintype "power_in"))
      (node (ref "U2") (pin "19") (pinfunction "DGND_19") (pintype "power_in"))
      (node (ref "U2") (pin "2") (pinfunction "AGND_2") (pintype "power_in"))
      (node (ref "U2") (pin "32") (pinfunction "TEST_32") (pintype "input"))
      (node (ref "U2") (pin "36") (pinfunction "IC_36") (pintype "passive"))
      (node (ref "U2") (pin "44") (pinfunction "DGND_44") (pintype "power_in"))
      (node (ref "U2") (pin "47") (pinfunction "DGND_47") (pintype "power_in"))
      (node (ref "U2") (pin "9") (pinfunction "IC_9") (pintype "passive"))
      (node (ref "U3") (pin "2") (pinfunction "C1_2") (pintype "passive"))
      (node (ref "U3") (pin "4") (pinfunction "C2_4") (pintype "passive"))
      (node (ref "U3") (pin "6") (pinfunction "C3_6") (pintype "passive"))
      (node (ref "U3") (pin "8") (pinfunction "C4_8") (pintype "passive"))
      (node (ref "Y1") (pin "2") (pinfunction "GND_2") (pintype "passive"))
      (node (ref "Y1") (pin "4") (pinfunction "GND_4") (pintype "passive"))
    )
    (net (code "34") (name "Net-(D1-Pad1)") (class "Default")
      (node (ref "D1") (pin "1") (pinfunction "1_1") (pintype "passive"))
      (node (ref "R14") (pin "1") (pinfunction "1_1") (pintype "passive"))
    )
    (net (code "35") (name "Net-(D2-Pad1)") (class "Default")
      (node (ref "D2") (pin "1") (pinfunction "1_1") (pintype "passive"))
      (node (ref "R15") (pin "2") (pinfunction "2_2") (pintype "passive"))
    )
    (net (code "36") (name "Net-(D3-Pad1)") (class "Default")
      (node (ref "D3") (pin "1") (pinfunction "1_1") (pintype "passive"))
      (node (ref "R16") (pin "2") (pinfunction "2_2") (pintype "passive"))
    )
    (net (code "37") (name "Net-(D4-Pad1)") (class "Default")
      (node (ref "D4") (pin "1") (pinfunction "1_1") (pintype "passive"))
      (node (ref "R17") (pin "2") (pinfunction "2_2") (pintype "passive"))
    )
    (net (code "38") (name "Net-(D5-Pad1)") (class "Default")
      (node (ref "D5") (pin "1") (pinfunction "1_1") (pintype "passive"))
      (node (ref "R61") (pin "1") (pinfunction "1_1") (pintype "passive"))
    )
    (net (code "39") (name "Net-(D6-Pad1)") (class "Default")
      (node (ref "D6") (pin "1") (pinfunction "1_1") (pintype "passive"))
      (node (ref "R62") (pin "1") (pinfunction "1_1") (pintype "passive"))
    )
    (net (code "40") (name "Net-(D7-Pad1)") (class "Default")
      (node (ref "D7") (pin "1") (pinfunction "1_1") (pintype "passive"))
      (node (ref "TR1") (pin "5") (pinfunction "5_5") (pintype "passive"))
    )
    (net (code "41") (name "Net-(D8-Pad1)") (class "Default")
      (node (ref "D8") (pin "1") (pinfunction "1_1") (pintype "passive"))
      (node (ref "TR1") (pin "7") (pinfunction "7_7") (pintype "passive"))
    )
    (net (code "42") (name "Net-(J1-sleeve)") (class "Default")
      (node (ref "J1") (pin "1") (pinfunction "sleeve_1") (pintype "passive"))
      (node (ref "R5") (pin "2") (pinfunction "2_2") (pintype "passive"))
      (node (ref "R7") (pin "1") (pinfunction "1_1") (pintype "passive"))
    )
    (net (code "43") (name "Net-(J1-tip)") (class "Default")
      (node (ref "J1") (pin "2") (pinfunction "tip_2") (pintype "passive"))
      (node (ref "R1") (pin "1") (pinfunction "1_1") (pintype "passive"))
      (node (ref "R3") (pin "1") (pinfunction "1_1") (pintype "passive"))
    )
    (net (code "44") (name "Net-(J3-sleeve)") (class "Default")
      (node (ref "J3") (pin "1") (pinfunction "sleeve_1") (pintype "passive"))
      (node (ref "R30") (pin "2") (pinfunction "2_2") (pintype "passive"))
      (node (ref "R35") (pin "1") (pinfunction "1_1") (pintype "passive"))
    )
    (net (code "45") (name "Net-(J3-tip)") (class "Default")
      (node (ref "J3") (pin "2") (pinfunction "tip_2") (pintype "passive"))
      (node (ref "R25") (pin "1") (pinfunction "1_1") (pintype "passive"))
      (node (ref "R27") (pin "1") (pinfunction "1_1") (pintype "passive"))
    )
    (net (code "46") (name "Net-(J4-Pad1)") (class "Default")
      (node (ref "J4") (pin "1") (pinfunction "1_1") (pintype "passive"))
      (node (ref "R39") (pin "2") (pinfunction "2_2") (pintype "passive"))
    )
    (net (code "47") (name "Net-(J5-Pad1)") (class "Default")
      (node (ref "J5") (pin "1") (pinfunction "1_1") (pintype "passive"))
      (node (ref "R47") (pin "2") (pinfunction "2_2") (pintype "passive"))
    )
    (net (code "48") (name "Net-(J6-Pad1)") (class "Default")
      (node (ref "J6") (pin "1") (pinfunction "1_1") (pintype "passive"))
      (node (ref "R55") (pin "2") (pinfunction "2_2") (pintype "passive"))
    )
    (net (code "49") (name "Net-(R37-Pad2)") (class "Default")
      (node (ref "R37") (pin "2") (pinfunction "2_2") (pintype "passive"))
      (node (ref "R38") (pin "1") (pinfunction "1_1") (pintype "passive"))
    )
    (net (code "50") (name "Net-(R38-Pad2)") (class "Default")
      (node (ref "R38") (pin "2") (pinfunction "2_2") (pintype "passive"))
      (node (ref "R39") (pin "1") (pinfunction "1_1") (pintype "passive"))
    )
    (net (code "51") (name "Net-(R45-Pad2)") (class "Default")
      (node (ref "R45") (pin "2") (pinfunction "2_2") (pintype "passive"))
      (node (ref "R46") (pin "1") (pinfunction "1_1") (pintype "passive"))
    )
    (net (code "52") (name "Net-(R46-Pad2)") (class "Default")
      (node (ref "R46") (pin "2") (pinfunction "2_2") (pintype "passive"))
      (node (ref "R47") (pin "1") (pinfunction "1_1") (pintype "passive"))
    )
    (net (code "53") (name "Net-(R53-Pad2)") (class "Default")
      (node (ref "R53") (pin "2") (pinfunction "2_2") (pintype "passive"))
      (node (ref "R54") (pin "1") (pinfunction "1_1") (pintype "passive"))
    )
    (net (code "54") (name "Net-(R54-Pad2)") (class "Default")
      (node (ref "R54") (pin "2") (pinfunction "2_2") (pintype "passive"))
      (node (ref "R55") (pin "1") (pinfunction "1_1") (pintype "passive"))
    )
    (net (code "55") (name "Net-(U1-A1)") (class "Default")
      (node (ref "R2") (pin "1") (pinfunction "1_1") (pintype "passive"))
      (node (ref "U1") (pin "1") (pinfunction "A1_1") (pintype "passive"))
    )
    (net (code "56") (name "Net-(U1-A2)") (class "Default")
      (node (ref "R4") (pin "1") (pinfunction "1_1") (pintype "passive"))
      (node (ref "U1") (pin "3") (pinfunction "A2_3") (pintype "passive"))
    )
    (net (code "57") (name "Net-(U1-A3)") (class "Default")
      (node (ref "R6") (pin "1") (pinfunction "1_1") (pintype "passive"))
      (node (ref "U1") (pin "5") (pinfunction "A3_5") (pintype "passive"))
    )
    (net (code "58") (name "Net-(U1-A4)") (class "Default")
      (node (ref "R8") (pin "1") (pinfunction "1_1") (pintype "passive"))
      (node (ref "U1") (pin "7") (pinfunction "A4_7") (pintype "passive"))
    )
    (net (code "59") (name "Net-(U2-CF1)") (class "Default")
      (node (ref "R17") (pin "1") (pinfunction "1_1") (pintype "passive"))
      (node (ref "U2") (pin "25") (pinfunction "CF1_25") (pintype "output"))
    )
    (net (code "60") (name "Net-(U2-CF2)") (class "Default")
      (node (ref "R16") (pin "1") (pinfunction "1_1") (pintype "passive"))
      (node (ref "U2") (pin "26") (pinfunction "CF2_26") (pintype "output"))
    )
    (net (code "61") (name "Net-(U2-CF3)") (class "Default")
      (node (ref "R15") (pin "1") (pinfunction "1_1") (pintype "passive"))
      (node (ref "U2") (pin "27") (pinfunction "CF3_27") (pintype "output"))
    )
    (net (code "62") (name "Net-(U2-CF4)") (class "Default")
      (node (ref "R14") (pin "2") (pinfunction "2_2") (pintype "passive"))
      (node (ref "U2") (pin "28") (pinfunction "CF4_28") (pintype "output"))
    )
    (net (code "63") (name "Net-(U2-OSCI)") (class "Default")
      (node (ref "U2") (pin "20") (pinfunction "OSCI_20") (pintype "input"))
      (node (ref "Y1") (pin "3") (pinfunction "3_3") (pintype "passive"))
    )
    (net (code "64") (name "Net-(U2-OSCO)") (class "Default")
      (node (ref "U2") (pin "21") (pinfunction "OSCO_21") (pintype "output"))
      (node (ref "Y1") (pin "1") (pinfunction "1_1") (pintype "passive"))
    )
    (net (code "65") (name "Net-(U2-V1N)") (class "Default")
      (node (ref "C10") (pin "2") (pinfunction "2_2") (pintype "passive"))
      (node (ref "R21") (pin "2") (pinfunction "2_2") (pintype "passive"))
      (node (ref "U2") (pin "14") (pinfunction "V1N_14") (pintype "passive"))
    )
    (net (code "66") (name "Net-(U2-V2N)") (class "Default")
      (node (ref "C12") (pin "2") (pinfunction "2_2") (pintype "passive"))
      (node (ref "R24") (pin "2") (pinfunction "2_2") (pintype "passive"))
      (node (ref "U2") (pin "16") (pinfunction "V2N_16") (pintype "passive"))
    )
    (net (code "67") (name "Net-(U2-V3N)") (class "Default")
      (node (ref "C13") (pin "2") (pinfunction "2_2") (pintype "passive"))
      (node (ref "R29") (pin "2") (pinfunction "2_2") (pintype "passive"))
      (node (ref "U2") (pin "18") (pinfunction "V3N_18") (pintype "passive"))
    )
    (net (code "68") (name "Net-(U2-Vref)") (class "Default")
      (node (ref "C7") (pin "2") (pinfunction "2_2") (pintype "passive"))
      (node (ref "C8") (pin "2") (pinfunction "2_2") (pintype "passive"))
      (node (ref "U2") (pin "11") (pinfunction "Vref_11") (pintype "power_in"))
    )
    (net (code "69") (name "Net-(U3-A1)") (class "Default")
      (node (ref "R20") (pin "1") (pinfunction "1_1") (pintype "passive"))
      (node (ref "U3") (pin "1") (pinfunction "A1_1") (pintype "passive"))
    )
    (net (code "70") (name "Net-(U3-A2)") (class "Default")
      (node (ref "R23") (pin "1") (pinfunction "1_1") (pintype "passive"))
      (node (ref "U3") (pin "3") (pinfunction "A2_3") (pintype "passive"))
    )
    (net (code "71") (name "Net-(U3-A3)") (class "Default")
      (node (ref "R26") (pin "1") (pinfunction "1_1") (pintype "passive"))
      (node (ref "U3") (pin "5") (pinfunction "A3_5") (pintype "passive"))
    )
    (net (code "72") (name "Net-(U3-A4)") (class "Default")
      (node (ref "R28") (pin "1") (pinfunction "1_1") (pintype "passive"))
      (node (ref "U3") (pin "7") (pinfunction "A4_7") (pintype "passive"))
    )
    (net (code "73") (name "Net-(U4-D1)") (class "Default")
      (node (ref "TR1") (pin "9") (pinfunction "9_9") (pintype "passive"))
      (node (ref "U4") (pin "1") (pinfunction "D1_1") (pintype "output"))
    )
    (net (code "74") (name "Net-(U4-D2)") (class "Default")
      (node (ref "TR1") (pin "1") (pinfunction "1_1") (pintype "passive"))
      (node (ref "U4") (pin "3") (pinfunction "D2_3") (pintype "output"))
    )
    (net (code "75") (name "Net-(y-sleeve)") (class "Default")
      (node (ref "R19") (pin "2") (pinfunction "2_2") (pintype "passive"))
      (node (ref "R22") (pin "1") (pinfunction "1_1") (pintype "passive"))
      (node (ref "y") (pin "1") (pinfunction "sleeve_1") (pintype "passive"))
    )
    (net (code "76") (name "Net-(y-tip)") (class "Default")
      (node (ref "R18") (pin "1") (pinfunction "1_1") (pintype "passive"))
      (node (ref "R9") (pin "1") (pinfunction "1_1") (pintype "passive"))
      (node (ref "y") (pin "2") (pinfunction "tip_2") (pintype "passive"))
    )
    (net (code "77") (name "unconnected-(J1-ring_1-Pad3)") (class "Default")
      (node (ref "J1") (pin "3") (pinfunction "ring_1_3") (pintype "passive"))
    )
    (net (code "78") (name "unconnected-(J1-ring_2-Pad4)") (class "Default")
      (node (ref "J1") (pin "4") (pinfunction "ring_2_4") (pintype "passive"))
    )
    (net (code "79") (name "unconnected-(J3-ring_1-Pad3)") (class "Default")
      (node (ref "J3") (pin "3") (pinfunction "ring_1_3") (pintype "passive"))
    )
    (net (code "80") (name "unconnected-(J3-ring_2-Pad4)") (class "Default")
      (node (ref "J3") (pin "4") (pinfunction "ring_2_4") (pintype "passive"))
    )
    (net (code "81") (name "unconnected-(U2-NC-Pad35)") (class "Default")
      (node (ref "U2") (pin "35") (pinfunction "NC_35") (pintype "passive+no_connect"))
    )
    (net (code "82") (name "unconnected-(U2-NC-Pad45)") (class "Default")
      (node (ref "U2") (pin "45") (pinfunction "NC_45") (pintype "passive+no_connect"))
    )
    (net (code "83") (name "unconnected-(U2-NC-Pad46)") (class "Default")
      (node (ref "U2") (pin "46") (pinfunction "NC_46") (pintype "passive+no_connect"))
    )
    (net (code "84") (name "unconnected-(U2-ZX0-Pad22)") (class "Default")
      (node (ref "U2") (pin "22") (pinfunction "ZX0_22") (pintype "output+no_connect"))
    )
    (net (code "85") (name "unconnected-(U2-ZX1-Pad23)") (class "Default")
      (node (ref "U2") (pin "23") (pinfunction "ZX1_23") (pintype "output+no_connect"))
    )
    (net (code "86") (name "unconnected-(U2-ZX2-Pad24)") (class "Default")
      (node (ref "U2") (pin "24") (pinfunction "ZX2_24") (pintype "output+no_connect"))
    )
    (net (code "87") (name "unconnected-(y-ring_1-Pad3)") (class "Default")
      (node (ref "y") (pin "3") (pinfunction "ring_1_3") (pintype "passive"))
    )
    (net (code "88") (name "unconnected-(y-ring_2-Pad4)") (class "Default")
      (node (ref "y") (pin "4") (pinfunction "ring_2_4") (pintype "passive"))
    )
  )
)
